# simreader_marble_hammi_FT230X.net
KiCad netlist of a schematic drawn in EAGLE
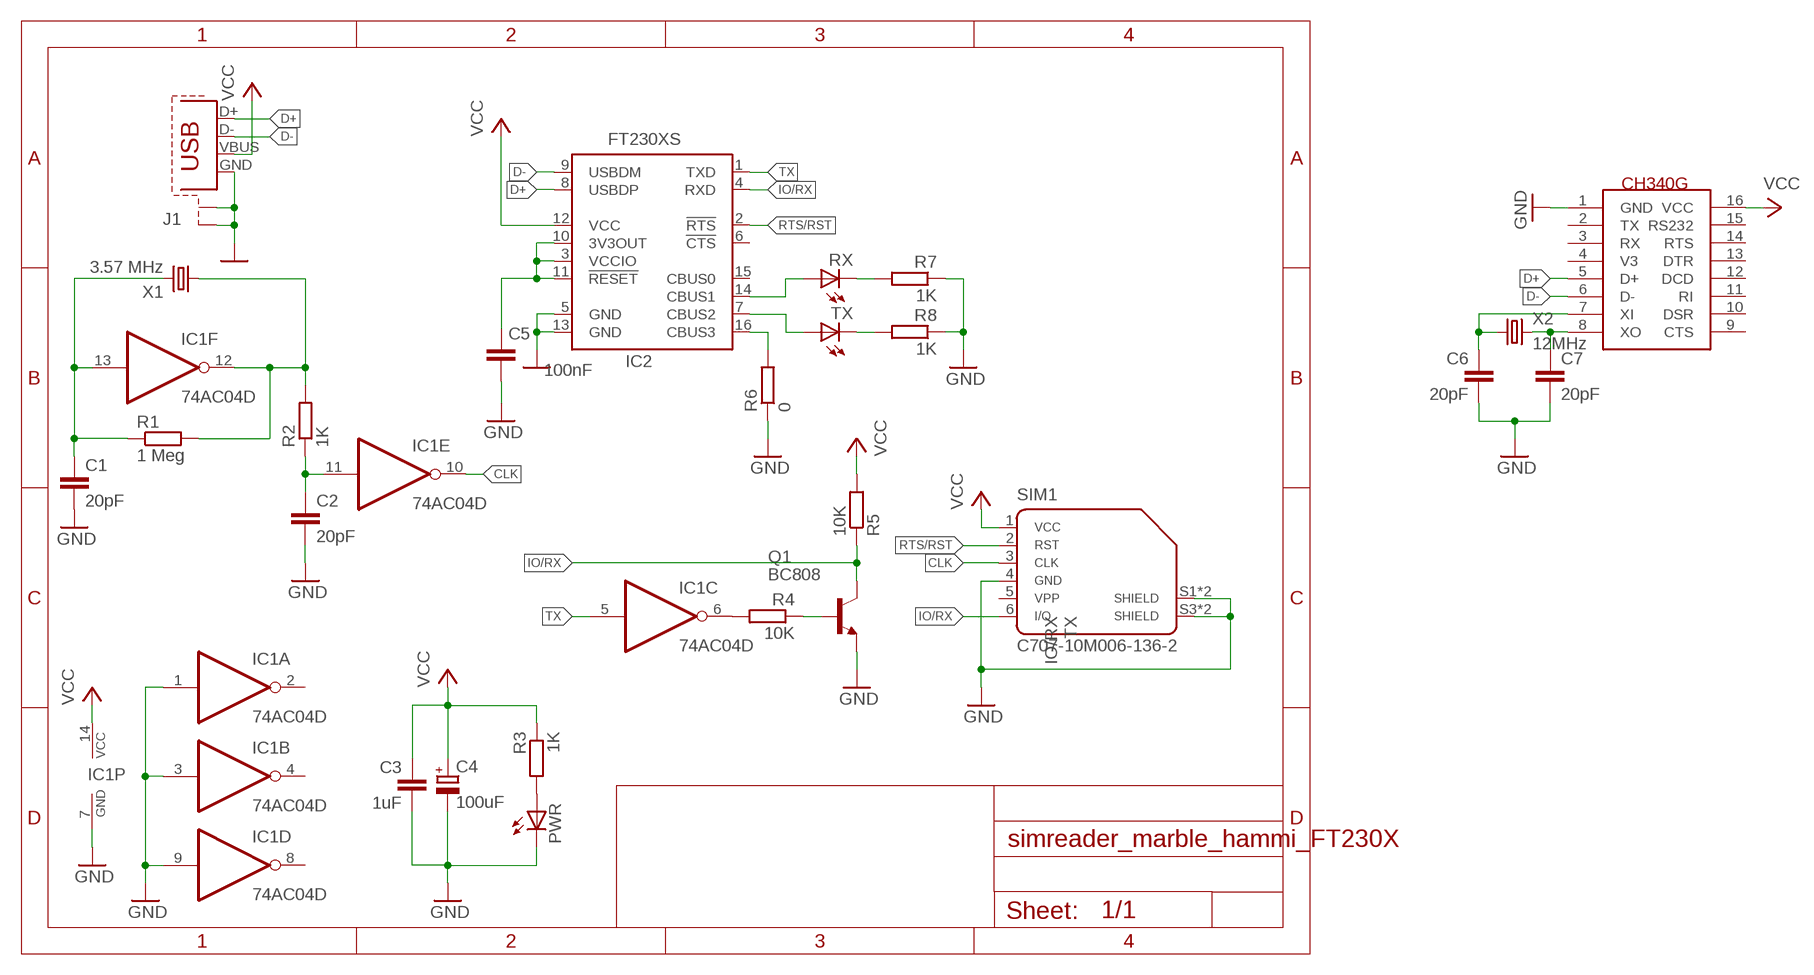
[diagram p0: schematic, sheet 1]

(export (version "E")
  (design (tool "Eeschema 10.0.6"))
  (components
    (comp (ref "C1")
      (value "20pF")
      (footprint "eagle-import:C0603")
      (libsource (lib "eagle-import") (part "C-EUC0603"))
    )
    (comp (ref "C2")
      (value "20pF")
      (footprint "eagle-import:C0603")
      (libsource (lib "eagle-import") (part "C-EUC0603"))
    )
    (comp (ref "C3")
      (value "1uF")
      (footprint "eagle-import:C0603")
      (libsource (lib "eagle-import") (part "C-EUC0603"))
    )
    (comp (ref "C4")
      (value "100uF")
      (footprint "eagle-import:140CLH-0810")
      (libsource (lib "eagle-import") (part "CPOL-EU140CLH-0810"))
    )
    (comp (ref "C5")
      (value "100nF")
      (footprint "eagle-import:C0603")
      (libsource (lib "eagle-import") (part "C-EUC0603"))
    )
    (comp (ref "C6")
      (value "20pF")
      (footprint "eagle-import:C0603")
      (libsource (lib "eagle-import") (part "C-EUC0603"))
    )
    (comp (ref "C7")
      (value "20pF")
      (footprint "eagle-import:C0603")
      (libsource (lib "eagle-import") (part "C-EUC0603"))
    )
    (comp (ref "IC1")
      (value "74AC04D")
      (footprint "eagle-import:SO14")
      (libsource (lib "eagle-import") (part "7404DAC"))
    )
    (comp (ref "IC2")
      (value "FT230XS")
      (footprint "eagle-import:SSOP-16")
      (libsource (lib "eagle-import") (part "FT230XS"))
    )
    (comp (ref "J1")
      (value "USB-SHIELD-A-H")
      (footprint "eagle-import:USB-A-H")
      (libsource (lib "eagle-import") (part "USB-SHIELD-A-H"))
    )
    (comp (ref "PWR")
      (value "LEDCHIPLED_0603")
      (footprint "eagle-import:CHIPLED_0603")
      (libsource (lib "eagle-import") (part "LEDCHIPLED_0603"))
    )
    (comp (ref "Q1")
      (value "BC808")
      (footprint "eagle-import:SOT23-BEC")
      (libsource (lib "eagle-import") (part "-NPN-SOT23-BECBC808"))
    )
    (comp (ref "R1")
      (value "1 Meg")
      (footprint "eagle-import:R0603")
      (libsource (lib "eagle-import") (part "R-EU_R0603"))
    )
    (comp (ref "R2")
      (value "1K")
      (footprint "eagle-import:R0603")
      (libsource (lib "eagle-import") (part "R-EU_R0603"))
    )
    (comp (ref "R3")
      (value "1K")
      (footprint "eagle-import:R0603")
      (libsource (lib "eagle-import") (part "R-EU_R0603"))
    )
    (comp (ref "R4")
      (value "10K")
      (footprint "eagle-import:R0603")
      (libsource (lib "eagle-import") (part "R-EU_R0603"))
    )
    (comp (ref "R5")
      (value "10K")
      (footprint "eagle-import:R0603")
      (libsource (lib "eagle-import") (part "R-EU_R0603"))
    )
    (comp (ref "R6")
      (value "0")
      (footprint "eagle-import:R0603")
      (libsource (lib "eagle-import") (part "R-EU_R0603"))
    )
    (comp (ref "R7")
      (value "1K")
      (footprint "eagle-import:R0603")
      (libsource (lib "eagle-import") (part "R-EU_R0603"))
    )
    (comp (ref "R8")
      (value "1K")
      (footprint "eagle-import:R0603")
      (libsource (lib "eagle-import") (part "R-EU_R0603"))
    )
    (comp (ref "RX")
      (value "LEDCHIPLED_0603")
      (footprint "eagle-import:CHIPLED_0603")
      (libsource (lib "eagle-import") (part "LEDCHIPLED_0603"))
    )
    (comp (ref "SIM1")
      (value "C707-10M006-136-2")
      (footprint "eagle-import:C707_10M006_136_2")
      (libsource (lib "eagle-import") (part "C707-10M006-136-2"))
    )
    (comp (ref "TX")
      (value "LEDCHIPLED_0603")
      (footprint "eagle-import:CHIPLED_0603")
      (libsource (lib "eagle-import") (part "LEDCHIPLED_0603"))
    )
    (comp (ref "U$1")
      (value "CH340G")
      (footprint "eagle-import:CH340G")
      (libsource (lib "eagle-import") (part "CH340G"))
    )
    (comp (ref "X1")
      (value "3.57 MHz")
      (footprint "eagle-import:HC49UP")
      (libsource (lib "eagle-import") (part "CRYSTALHC49UP"))
    )
    (comp (ref "X2")
      (value "12MHz")
      (footprint "eagle-import:HC49UP")
      (libsource (lib "eagle-import") (part "CRYSTALHC49UP"))
    )
  )
  (nets
    (net (code "1") (name "CLK") (class "Default")
      (node (ref "IC1") (pin "10") (pinfunction "O_10") (pintype "output"))
      (node (ref "SIM1") (pin "3") (pinfunction "3_3") (pintype "passive"))
    )
    (net (code "2") (name "D+") (class "Default")
      (node (ref "IC2") (pin "8") (pinfunction "USBDP_8") (pintype "bidirectional"))
      (node (ref "J1") (pin "D+") (pinfunction "D+_D+") (pintype "passive"))
      (node (ref "U$1") (pin "5") (pinfunction "D+_5") (pintype "bidirectional"))
    )
    (net (code "3") (name "D-") (class "Default")
      (node (ref "IC2") (pin "9") (pinfunction "USBDM_9") (pintype "bidirectional"))
      (node (ref "J1") (pin "D-") (pinfunction "D-_D-") (pintype "passive"))
      (node (ref "U$1") (pin "6") (pinfunction "D-_6") (pintype "bidirectional"))
    )
    (net (code "4") (name "GND") (class "Default")
      (node (ref "C1") (pin "2") (pinfunction "2_2") (pintype "passive"))
      (node (ref "C2") (pin "2") (pinfunction "2_2") (pintype "passive"))
      (node (ref "C3") (pin "2") (pinfunction "2_2") (pintype "passive"))
      (node (ref "C4") (pin "-") (pinfunction "-_-") (pintype "passive"))
      (node (ref "C5") (pin "2") (pinfunction "2_2") (pintype "passive"))
      (node (ref "C6") (pin "2") (pinfunction "2_2") (pintype "passive"))
      (node (ref "C7") (pin "2") (pinfunction "2_2") (pintype "passive"))
      (node (ref "IC1") (pin "1") (pinfunction "I_1") (pintype "input"))
      (node (ref "IC1") (pin "3") (pinfunction "I_3") (pintype "input"))
      (node (ref "IC1") (pin "7") (pinfunction "GND_7") (pintype "power_in"))
      (node (ref "IC1") (pin "9") (pinfunction "I_9") (pintype "input"))
      (node (ref "IC2") (pin "13") (pinfunction "GND_13") (pintype "power_in"))
      (node (ref "IC2") (pin "5") (pinfunction "GND_5") (pintype "power_in"))
      (node (ref "J1") (pin "GND") (pinfunction "GND_GND") (pintype "passive"))
      (node (ref "J1") (pin "GND2") (pinfunction "S1_GND2") (pintype "passive"))
      (node (ref "J1") (pin "GND3") (pinfunction "S2_GND3") (pintype "passive"))
      (node (ref "PWR") (pin "C") (pinfunction "C_C") (pintype "passive"))
      (node (ref "Q1") (pin "E") (pinfunction "E_E") (pintype "passive"))
      (node (ref "R6") (pin "1") (pinfunction "1_1") (pintype "passive"))
      (node (ref "R7") (pin "1") (pinfunction "1_1") (pintype "passive"))
      (node (ref "R8") (pin "1") (pinfunction "1_1") (pintype "passive"))
      (node (ref "SIM1") (pin "4") (pinfunction "4_4") (pintype "passive"))
      (node (ref "SIM1") (pin "S1") (pinfunction "S1_S1") (pintype "passive"))
      (node (ref "SIM1") (pin "S2") (pinfunction "S1_S2") (pintype "passive"))
      (node (ref "SIM1") (pin "S3") (pinfunction "S2_S3") (pintype "passive"))
      (node (ref "SIM1") (pin "S4") (pinfunction "S2_S4") (pintype "passive"))
      (node (ref "U$1") (pin "1") (pinfunction "GND_1") (pintype "bidirectional"))
    )
    (net (code "5") (name "IO{slash}RX") (class "Default")
      (node (ref "IC2") (pin "4") (pinfunction "RXD_4") (pintype "input"))
      (node (ref "Q1") (pin "C") (pinfunction "C_C") (pintype "passive"))
      (node (ref "R5") (pin "1") (pinfunction "1_1") (pintype "passive"))
      (node (ref "SIM1") (pin "6") (pinfunction "6_6") (pintype "passive"))
    )
    (net (code "6") (name "Net-(IC1C-O)") (class "Default")
      (node (ref "IC1") (pin "6") (pinfunction "O_6") (pintype "output"))
      (node (ref "R4") (pin "2") (pinfunction "2_2") (pintype "passive"))
    )
    (net (code "7") (name "Net-(IC1E-I)") (class "Default")
      (node (ref "C2") (pin "1") (pinfunction "1_1") (pintype "passive"))
      (node (ref "IC1") (pin "11") (pinfunction "I_11") (pintype "input"))
      (node (ref "R2") (pin "1") (pinfunction "1_1") (pintype "passive"))
    )
    (net (code "8") (name "Net-(IC1F-I)") (class "Default")
      (node (ref "C1") (pin "1") (pinfunction "1_1") (pintype "passive"))
      (node (ref "IC1") (pin "13") (pinfunction "I_13") (pintype "input"))
      (node (ref "R1") (pin "1") (pinfunction "1_1") (pintype "passive"))
      (node (ref "X1") (pin "2") (pinfunction "2_2") (pintype "passive"))
    )
    (net (code "9") (name "Net-(IC1F-O)") (class "Default")
      (node (ref "IC1") (pin "12") (pinfunction "O_12") (pintype "output"))
      (node (ref "R1") (pin "2") (pinfunction "2_2") (pintype "passive"))
      (node (ref "R2") (pin "2") (pinfunction "2_2") (pintype "passive"))
      (node (ref "X1") (pin "1") (pinfunction "1_1") (pintype "passive"))
    )
    (net (code "10") (name "Net-(IC2-3V3OUT)") (class "Default")
      (node (ref "C5") (pin "1") (pinfunction "1_1") (pintype "passive"))
      (node (ref "IC2") (pin "10") (pinfunction "3V3OUT_10") (pintype "output"))
      (node (ref "IC2") (pin "11") (pinfunction "~{RESET}_11") (pintype "input"))
      (node (ref "IC2") (pin "3") (pinfunction "VCCIO_3") (pintype "power_in"))
    )
    (net (code "11") (name "Net-(IC2-CBUS1)") (class "Default")
      (node (ref "IC2") (pin "14") (pinfunction "CBUS1_14") (pintype "bidirectional"))
      (node (ref "RX") (pin "A") (pinfunction "A_A") (pintype "passive"))
    )
    (net (code "12") (name "Net-(IC2-CBUS2)") (class "Default")
      (node (ref "IC2") (pin "7") (pinfunction "CBUS2_7") (pintype "bidirectional"))
      (node (ref "TX") (pin "A") (pinfunction "A_A") (pintype "passive"))
    )
    (net (code "13") (name "Net-(IC2-CBUS3)") (class "Default")
      (node (ref "IC2") (pin "16") (pinfunction "CBUS3_16") (pintype "bidirectional"))
      (node (ref "R6") (pin "2") (pinfunction "2_2") (pintype "passive"))
    )
    (net (code "14") (name "Net-(PWR-PadA)") (class "Default")
      (node (ref "PWR") (pin "A") (pinfunction "A_A") (pintype "passive"))
      (node (ref "R3") (pin "2") (pinfunction "2_2") (pintype "passive"))
    )
    (net (code "15") (name "Net-(Q1-PadB)") (class "Default")
      (node (ref "Q1") (pin "B") (pinfunction "B_B") (pintype "passive"))
      (node (ref "R4") (pin "1") (pinfunction "1_1") (pintype "passive"))
    )
    (net (code "16") (name "Net-(R7-Pad2)") (class "Default")
      (node (ref "R7") (pin "2") (pinfunction "2_2") (pintype "passive"))
      (node (ref "RX") (pin "C") (pinfunction "C_C") (pintype "passive"))
    )
    (net (code "17") (name "Net-(R8-Pad2)") (class "Default")
      (node (ref "R8") (pin "2") (pinfunction "2_2") (pintype "passive"))
      (node (ref "TX") (pin "C") (pinfunction "C_C") (pintype "passive"))
    )
    (net (code "18") (name "Net-(U$1-XI)") (class "Default")
      (node (ref "C6") (pin "1") (pinfunction "1_1") (pintype "passive"))
      (node (ref "U$1") (pin "7") (pinfunction "XI_7") (pintype "bidirectional"))
      (node (ref "X2") (pin "1") (pinfunction "1_1") (pintype "passive"))
    )
    (net (code "19") (name "Net-(U$1-XO)") (class "Default")
      (node (ref "C7") (pin "1") (pinfunction "1_1") (pintype "passive"))
      (node (ref "U$1") (pin "8") (pinfunction "XO_8") (pintype "bidirectional"))
      (node (ref "X2") (pin "2") (pinfunction "2_2") (pintype "passive"))
    )
    (net (code "20") (name "RTS{slash}RST") (class "Default")
      (node (ref "IC2") (pin "2") (pinfunction "~{RTS}_2") (pintype "output"))
      (node (ref "SIM1") (pin "2") (pinfunction "2_2") (pintype "passive"))
    )
    (net (code "21") (name "TX") (class "Default")
      (node (ref "IC1") (pin "5") (pinfunction "I_5") (pintype "input"))
      (node (ref "IC2") (pin "1") (pinfunction "TXD_1") (pintype "output"))
    )
    (net (code "22") (name "VCC") (class "Default")
      (node (ref "C3") (pin "1") (pinfunction "1_1") (pintype "passive"))
      (node (ref "C4") (pin "+") (pinfunction "+_+") (pintype "passive"))
      (node (ref "IC1") (pin "14") (pinfunction "VCC_14") (pintype "power_in"))
      (node (ref "IC2") (pin "12") (pinfunction "VCC_12") (pintype "power_in"))
      (node (ref "J1") (pin "VBUS") (pinfunction "VBUS_VBUS") (pintype "passive"))
      (node (ref "R3") (pin "1") (pinfunction "1_1") (pintype "passive"))
      (node (ref "R5") (pin "2") (pinfunction "2_2") (pintype "passive"))
      (node (ref "SIM1") (pin "1") (pinfunction "1_1") (pintype "passive"))
      (node (ref "U$1") (pin "16") (pinfunction "VCC_16") (pintype "bidirectional"))
    )
    (net (code "23") (name "unconnected-(IC1A-O-Pad2)") (class "Default")
      (node (ref "IC1") (pin "2") (pinfunction "O_2") (pintype "output"))
    )
    (net (code "24") (name "unconnected-(IC1B-O-Pad4)") (class "Default")
      (node (ref "IC1") (pin "4") (pinfunction "O_4") (pintype "output"))
    )
    (net (code "25") (name "unconnected-(IC1D-O-Pad8)") (class "Default")
      (node (ref "IC1") (pin "8") (pinfunction "O_8") (pintype "output"))
    )
    (net (code "26") (name "unconnected-(IC2-CBUS0-Pad15)") (class "Default")
      (node (ref "IC2") (pin "15") (pinfunction "CBUS0_15") (pintype "bidirectional"))
    )
    (net (code "27") (name "unconnected-(IC2-~{CTS}-Pad6)") (class "Default")
      (node (ref "IC2") (pin "6") (pinfunction "~{CTS}_6") (pintype "input"))
    )
    (net (code "28") (name "unconnected-(SIM1-Pad5)") (class "Default")
      (node (ref "SIM1") (pin "5") (pinfunction "5_5") (pintype "passive"))
    )
    (net (code "29") (name "unconnected-(U$1-CTS-Pad9)") (class "Default")
      (node (ref "U$1") (pin "9") (pinfunction "CTS_9") (pintype "bidirectional"))
    )
    (net (code "30") (name "unconnected-(U$1-DCD-Pad12)") (class "Default")
      (node (ref "U$1") (pin "12") (pinfunction "DCD_12") (pintype "bidirectional"))
    )
    (net (code "31") (name "unconnected-(U$1-DSR-Pad10)") (class "Default")
      (node (ref "U$1") (pin "10") (pinfunction "DSR_10") (pintype "bidirectional"))
    )
    (net (code "32") (name "unconnected-(U$1-DTR-Pad13)") (class "Default")
      (node (ref "U$1") (pin "13") (pinfunction "DTR_13") (pintype "bidirectional"))
    )
    (net (code "33") (name "unconnected-(U$1-RI-Pad11)") (class "Default")
      (node (ref "U$1") (pin "11") (pinfunction "RI_11") (pintype "bidirectional"))
    )
    (net (code "34") (name "unconnected-(U$1-RS232-Pad15)") (class "Default")
      (node (ref "U$1") (pin "15") (pinfunction "RS232_15") (pintype "bidirectional"))
    )
    (net (code "35") (name "unconnected-(U$1-RTS-Pad14)") (class "Default")
      (node (ref "U$1") (pin "14") (pinfunction "RTS_14") (pintype "bidirectional"))
    )
    (net (code "36") (name "unconnected-(U$1-RX-Pad3)") (class "Default")
      (node (ref "U$1") (pin "3") (pinfunction "RX_3") (pintype "bidirectional"))
    )
    (net (code "37") (name "unconnected-(U$1-TX-Pad2)") (class "Default")
      (node (ref "U$1") (pin "2") (pinfunction "TX_2") (pintype "bidirectional"))
    )
    (net (code "38") (name "unconnected-(U$1-V3-Pad4)") (class "Default")
      (node (ref "U$1") (pin "4") (pinfunction "V3_4") (pintype "bidirectional"))
    )
  )
)
